# GimbalFPV.net
KiCad netlist of a schematic drawn in Altium Designer
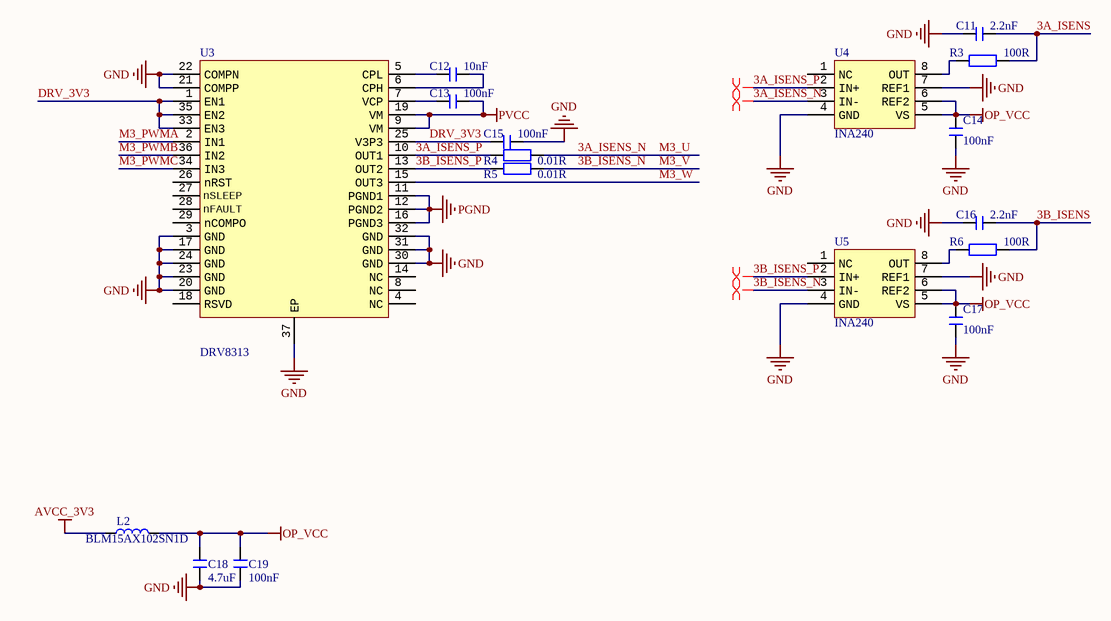
[diagram p0: GimbalFPV.SchDoc]

(export (version "E")
  (design (tool "Eeschema 10.0.6"))
  (components
    (comp (ref "C11")
      (value "2.2nF")
      (footprint "C 0402_L")
      (description "无极性贴片电容")
      (fields (field (name "版权归属") "源创客"))
      (libsource (lib "3.1   - 电阻-电容-电感") (part "C"))
    )
    (comp (ref "C12")
      (value "10nF")
      (footprint "C 0402_L")
      (description "无极性贴片电容")
      (fields (field (name "版权归属") "源创客"))
      (libsource (lib "3.1   - 电阻-电容-电感") (part "C"))
    )
    (comp (ref "C13")
      (value "100nF")
      (footprint "C 0402_L")
      (description "无极性贴片电容")
      (fields (field (name "版权归属") "源创客"))
      (libsource (lib "3.1   - 电阻-电容-电感") (part "C"))
    )
    (comp (ref "C14")
      (value "100nF")
      (footprint "C 0402_L")
      (description "无极性贴片电容")
      (fields (field (name "版权归属") "源创客"))
      (libsource (lib "3.1   - 电阻-电容-电感") (part "C"))
    )
    (comp (ref "C15")
      (value "100nF")
      (footprint "C 0402_L")
      (description "无极性贴片电容")
      (fields (field (name "版权归属") "源创客"))
      (libsource (lib "3.1   - 电阻-电容-电感") (part "C"))
    )
    (comp (ref "C16")
      (value "2.2nF")
      (footprint "C 0402_L")
      (description "无极性贴片电容")
      (fields (field (name "版权归属") "源创客"))
      (libsource (lib "3.1   - 电阻-电容-电感") (part "C"))
    )
    (comp (ref "C17")
      (value "100nF")
      (footprint "C 0402_L")
      (description "无极性贴片电容")
      (fields (field (name "版权归属") "源创客"))
      (libsource (lib "3.1   - 电阻-电容-电感") (part "C"))
    )
    (comp (ref "C18")
      (value "4.7uF")
      (footprint "C 0402_L")
      (description "无极性贴片电容")
      (fields (field (name "版权归属") "源创客"))
      (libsource (lib "3.1   - 电阻-电容-电感") (part "C"))
    )
    (comp (ref "C19")
      (value "100nF")
      (footprint "C 0402_L")
      (description "无极性贴片电容")
      (fields (field (name "版权归属") "源创客"))
      (libsource (lib "3.1   - 电阻-电容-电感") (part "C"))
    )
    (comp (ref "L2")
      (value "BLM15AX102SN1D")
      (footprint "L 0402")
      (description "小功率贴片电感")
      (fields (field (name "版权归属") "源创客"))
      (libsource (lib "3.1   - 电阻-电容-电感") (part "L"))
    )
    (comp (ref "R3")
      (value "100R")
      (footprint "R 0402_L")
      (description "贴片电阻")
      (fields (field (name "版权归属") "源创客"))
      (libsource (lib "3.1   - 电阻-电容-电感") (part "R"))
    )
    (comp (ref "R4")
      (value "0.01R")
      (footprint "RI 1206")
      (description "电流检测电阻")
      (fields (field (name "版权归属") "源创客"))
      (libsource (lib "3.1   - 电阻-电容-电感") (part "R-I"))
    )
    (comp (ref "R5")
      (value "0.01R")
      (footprint "RI 1206")
      (description "电流检测电阻")
      (fields (field (name "版权归属") "源创客"))
      (libsource (lib "3.1   - 电阻-电容-电感") (part "R-I"))
    )
    (comp (ref "R6")
      (value "100R")
      (footprint "R 0402_L")
      (description "贴片电阻")
      (fields (field (name "版权归属") "源创客"))
      (libsource (lib "3.1   - 电阻-电容-电感") (part "R"))
    )
    (comp (ref "U3")
      (value "DRV8313")
      (footprint "VQFN-36-6X6")
      (description "集成FET的3路半桥驱动器\r\n3A")
      (libsource (lib "1.1   - IC芯片") (part "DRV8313"))
    )
    (comp (ref "U4")
      (value "INA240")
      (footprint "SSOP8_L")
      (description "PWM抑制电流检测芯片")
      (libsource (lib "1.1   - IC芯片") (part "INA240"))
    )
    (comp (ref "U5")
      (value "INA240")
      (footprint "SSOP8_L")
      (description "PWM抑制电流检测芯片")
      (libsource (lib "1.1   - IC芯片") (part "INA240"))
    )
  )
  (nets
    (net (code "1") (name "/3A_ISENS") (class "Default")
      (node (ref "C11") (pin "2") (pinfunction "2_2") (pintype "passive"))
      (node (ref "R3") (pin "2") (pinfunction "2_2") (pintype "passive"))
    )
    (net (code "2") (name "/3A_ISENS_N") (class "Default")
      (node (ref "R4") (pin "2") (pinfunction "2_2") (pintype "passive"))
      (node (ref "U4") (pin "3") (pinfunction "IN-_3") (pintype "passive"))
    )
    (net (code "3") (name "/3A_ISENS_P") (class "Default")
      (node (ref "R4") (pin "1") (pinfunction "1_1") (pintype "passive"))
      (node (ref "U3") (pin "10") (pinfunction "OUT1_10") (pintype "passive"))
      (node (ref "U4") (pin "2") (pinfunction "IN+_2") (pintype "passive"))
    )
    (net (code "4") (name "/3B_ISENS") (class "Default")
      (node (ref "C16") (pin "2") (pinfunction "2_2") (pintype "passive"))
      (node (ref "R6") (pin "2") (pinfunction "2_2") (pintype "passive"))
    )
    (net (code "5") (name "/3B_ISENS_N") (class "Default")
      (node (ref "R5") (pin "2") (pinfunction "2_2") (pintype "passive"))
      (node (ref "U5") (pin "3") (pinfunction "IN-_3") (pintype "passive"))
    )
    (net (code "6") (name "/3B_ISENS_P") (class "Default")
      (node (ref "R5") (pin "1") (pinfunction "1_1") (pintype "passive"))
      (node (ref "U3") (pin "13") (pinfunction "OUT2_13") (pintype "passive"))
      (node (ref "U5") (pin "2") (pinfunction "IN+_2") (pintype "passive"))
    )
    (net (code "7") (name "/DRV_3V3") (class "Default")
      (node (ref "C15") (pin "1") (pinfunction "1_1") (pintype "passive"))
      (node (ref "U3") (pin "1") (pinfunction "EN1_1") (pintype "passive"))
      (node (ref "U3") (pin "25") (pinfunction "V3P3_25") (pintype "passive"))
      (node (ref "U3") (pin "33") (pinfunction "EN3_33") (pintype "passive"))
      (node (ref "U3") (pin "35") (pinfunction "EN2_35") (pintype "passive"))
    )
    (net (code "8") (name "/M3_PWMA") (class "Default")
      (node (ref "U3") (pin "2") (pinfunction "IN1_2") (pintype "passive"))
    )
    (net (code "9") (name "/M3_PWMB") (class "Default")
      (node (ref "U3") (pin "36") (pinfunction "IN2_36") (pintype "passive"))
    )
    (net (code "10") (name "/M3_PWMC") (class "Default")
      (node (ref "U3") (pin "34") (pinfunction "IN3_34") (pintype "passive"))
    )
    (net (code "11") (name "/M3_W") (class "Default")
      (node (ref "U3") (pin "15") (pinfunction "OUT3_15") (pintype "passive"))
    )
    (net (code "12") (name "AVCC_3V3") (class "Default")
      (node (ref "L2") (pin "1") (pinfunction "1_1") (pintype "passive"))
    )
    (net (code "13") (name "GND") (class "Default")
      (node (ref "C11") (pin "1") (pinfunction "1_1") (pintype "passive"))
      (node (ref "C14") (pin "1") (pinfunction "1_1") (pintype "passive"))
      (node (ref "C15") (pin "2") (pinfunction "2_2") (pintype "passive"))
      (node (ref "C16") (pin "1") (pinfunction "1_1") (pintype "passive"))
      (node (ref "C17") (pin "1") (pinfunction "1_1") (pintype "passive"))
      (node (ref "C18") (pin "1") (pinfunction "1_1") (pintype "passive"))
      (node (ref "C19") (pin "1") (pinfunction "1_1") (pintype "passive"))
      (node (ref "U3") (pin "17") (pinfunction "GND_17") (pintype "passive"))
      (node (ref "U3") (pin "20") (pinfunction "GND_20") (pintype "passive"))
      (node (ref "U3") (pin "21") (pinfunction "COMPP_21") (pintype "passive"))
      (node (ref "U3") (pin "22") (pinfunction "COMPN_22") (pintype "passive"))
      (node (ref "U3") (pin "23") (pinfunction "GND_23") (pintype "passive"))
      (node (ref "U3") (pin "24") (pinfunction "GND_24") (pintype "passive"))
      (node (ref "U3") (pin "3") (pinfunction "GND_3") (pintype "passive"))
      (node (ref "U3") (pin "30") (pinfunction "GND_30") (pintype "passive"))
      (node (ref "U3") (pin "31") (pinfunction "GND_31") (pintype "passive"))
      (node (ref "U3") (pin "32") (pinfunction "GND_32") (pintype "passive"))
      (node (ref "U3") (pin "37") (pinfunction "EP_37") (pintype "passive"))
      (node (ref "U4") (pin "4") (pinfunction "GND_4") (pintype "passive"))
      (node (ref "U4") (pin "7") (pinfunction "REF1_7") (pintype "passive"))
      (node (ref "U5") (pin "4") (pinfunction "GND_4") (pintype "passive"))
      (node (ref "U5") (pin "7") (pinfunction "REF1_7") (pintype "passive"))
    )
    (net (code "14") (name "Net-(U3-CPH)") (class "Default")
      (node (ref "C12") (pin "2") (pinfunction "2_2") (pintype "passive"))
      (node (ref "U3") (pin "6") (pinfunction "CPH_6") (pintype "passive"))
    )
    (net (code "15") (name "Net-(U3-CPL)") (class "Default")
      (node (ref "C12") (pin "1") (pinfunction "1_1") (pintype "passive"))
      (node (ref "U3") (pin "5") (pinfunction "CPL_5") (pintype "passive"))
    )
    (net (code "16") (name "Net-(U3-VCP)") (class "Default")
      (node (ref "C13") (pin "1") (pinfunction "1_1") (pintype "passive"))
      (node (ref "U3") (pin "7") (pinfunction "VCP_7") (pintype "passive"))
    )
    (net (code "17") (name "Net-(U4-OUT)") (class "Default")
      (node (ref "R3") (pin "1") (pinfunction "1_1") (pintype "passive"))
      (node (ref "U4") (pin "8") (pinfunction "OUT_8") (pintype "passive"))
    )
    (net (code "18") (name "Net-(U5-OUT)") (class "Default")
      (node (ref "R6") (pin "1") (pinfunction "1_1") (pintype "passive"))
      (node (ref "U5") (pin "8") (pinfunction "OUT_8") (pintype "passive"))
    )
    (net (code "19") (name "OP_VCC") (class "Default")
      (node (ref "C14") (pin "2") (pinfunction "2_2") (pintype "passive"))
      (node (ref "C17") (pin "2") (pinfunction "2_2") (pintype "passive"))
      (node (ref "C18") (pin "2") (pinfunction "2_2") (pintype "passive"))
      (node (ref "C19") (pin "2") (pinfunction "2_2") (pintype "passive"))
      (node (ref "L2") (pin "2") (pinfunction "2_2") (pintype "passive"))
      (node (ref "U4") (pin "5") (pinfunction "VS_5") (pintype "passive"))
      (node (ref "U4") (pin "6") (pinfunction "REF2_6") (pintype "passive"))
      (node (ref "U5") (pin "5") (pinfunction "VS_5") (pintype "passive"))
      (node (ref "U5") (pin "6") (pinfunction "REF2_6") (pintype "passive"))
    )
    (net (code "20") (name "PGND") (class "Default")
      (node (ref "U3") (pin "11") (pinfunction "PGND1_11") (pintype "passive"))
      (node (ref "U3") (pin "12") (pinfunction "PGND2_12") (pintype "passive"))
      (node (ref "U3") (pin "16") (pinfunction "PGND3_16") (pintype "passive"))
    )
    (net (code "21") (name "PVCC") (class "Default")
      (node (ref "C13") (pin "2") (pinfunction "2_2") (pintype "passive"))
      (node (ref "U3") (pin "19") (pinfunction "VM_19") (pintype "passive"))
      (node (ref "U3") (pin "9") (pinfunction "VM_9") (pintype "passive"))
    )
    (net (code "22") (name "unconnected-(U3-NC-Pad4)") (class "Default")
      (node (ref "U3") (pin "4") (pinfunction "NC_4") (pintype "passive"))
    )
    (net (code "23") (name "unconnected-(U3-NC-Pad8)") (class "Default")
      (node (ref "U3") (pin "8") (pinfunction "NC_8") (pintype "passive"))
    )
    (net (code "24") (name "unconnected-(U3-NC-Pad14)") (class "Default")
      (node (ref "U3") (pin "14") (pinfunction "NC_14") (pintype "passive"))
    )
    (net (code "25") (name "unconnected-(U3-RSVD-Pad18)") (class "Default")
      (node (ref "U3") (pin "18") (pinfunction "RSVD_18") (pintype "passive"))
    )
    (net (code "26") (name "unconnected-(U3-nCOMPO-Pad29)") (class "Default")
      (node (ref "U3") (pin "29") (pinfunction "nCOMPO_29") (pintype "passive"))
    )
    (net (code "27") (name "unconnected-(U3-nFAULT-Pad28)") (class "Default")
      (node (ref "U3") (pin "28") (pinfunction "nFAULT_28") (pintype "passive"))
    )
    (net (code "28") (name "unconnected-(U3-nRST-Pad26)") (class "Default")
      (node (ref "U3") (pin "26") (pinfunction "nRST_26") (pintype "passive"))
    )
    (net (code "29") (name "unconnected-(U3-nSLEEP-Pad27)") (class "Default")
      (node (ref "U3") (pin "27") (pinfunction "nSLEEP_27") (pintype "passive"))
    )
    (net (code "30") (name "unconnected-(U4-NC-Pad1)") (class "Default")
      (node (ref "U4") (pin "1") (pinfunction "NC_1") (pintype "passive"))
    )
    (net (code "31") (name "unconnected-(U5-NC-Pad1)") (class "Default")
      (node (ref "U5") (pin "1") (pinfunction "NC_1") (pintype "passive"))
    )
  )
)
